# MCU.net
KiCad netlist of a schematic drawn in Altium Designer
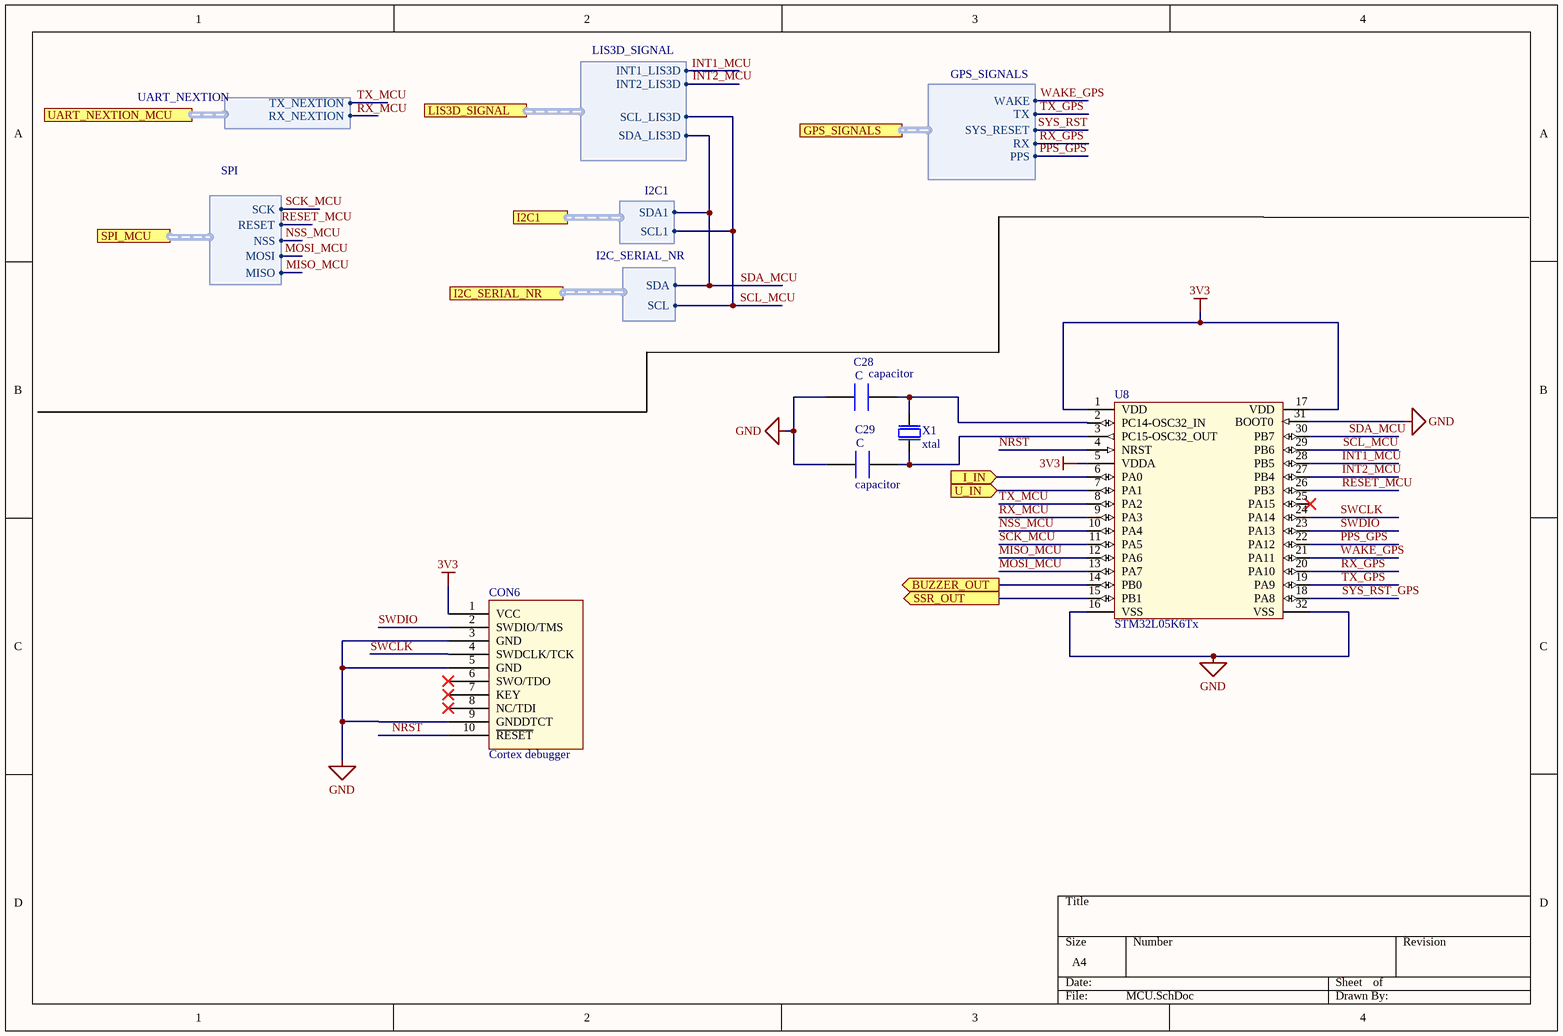
[diagram p0: MCU.SchDoc]

(export (version "E")
  (design (tool "Eeschema 10.0.6"))
  (components
    (comp (ref "C28")
      (value "capacitor")
      (footprint "CAPC1005X04L")
      (libsource (lib "pasives") (part "capacitor"))
    )
    (comp (ref "C29")
      (value "capacitor")
      (footprint "CAPC1005X04L")
      (libsource (lib "pasives") (part "capacitor"))
    )
    (comp (ref "CON6")
      (value "Cortex debugger")
      (footprint "Jtag header")
      (libsource (lib "conector's_and_TP") (part "Cortex debugger"))
    )
    (comp (ref "U8") (value "STM32L05K6Tx") (libsource (lib "halfgelijders") (part "STM32L05K6Tx")))
    (comp (ref "X1") (value "xtal") (footprint "BT-XTAL_2016") (libsource (lib "pasives") (part "xtal")))
  )
  (nets
    (net (code "9") (name "/BUZZER_OUT") (class "Default")
      (node (ref "U8") (pin "14") (pinfunction "PB0_14") (pintype "bidirectional"))
    )
    (net (code "11") (name "/INT1_MCU") (class "Default")
      (node (ref "U8") (pin "28") (pinfunction "PB5_28") (pintype "bidirectional"))
    )
    (net (code "12") (name "/INT2_MCU") (class "Default")
      (node (ref "U8") (pin "27") (pinfunction "PB4_27") (pintype "bidirectional"))
    )
    (net (code "13") (name "/I_IN") (class "Default")
      (node (ref "U8") (pin "6") (pinfunction "PA0_6") (pintype "bidirectional"))
    )
    (net (code "15") (name "/MISO_MCU") (class "Default")
      (node (ref "U8") (pin "12") (pinfunction "PA6_12") (pintype "bidirectional"))
    )
    (net (code "16") (name "/MOSI_MCU") (class "Default")
      (node (ref "U8") (pin "13") (pinfunction "PA7_13") (pintype "bidirectional"))
    )
    (net (code "17") (name "/NRST") (class "Default")
      (node (ref "CON6") (pin "10") (pinfunction "~{RESET}_10") (pintype "passive"))
      (node (ref "U8") (pin "4") (pinfunction "NRST_4") (pintype "input"))
    )
    (net (code "18") (name "/NSS_MCU") (class "Default")
      (node (ref "U8") (pin "10") (pinfunction "PA4_10") (pintype "bidirectional"))
    )
    (net (code "19") (name "/PPS_GPS") (class "Default")
      (node (ref "U8") (pin "22") (pinfunction "PA12_22") (pintype "bidirectional"))
    )
    (net (code "20") (name "/RESET_MCU") (class "Default")
      (node (ref "U8") (pin "26") (pinfunction "PB3_26") (pintype "bidirectional"))
    )
    (net (code "21") (name "/RX_GPS") (class "Default")
      (node (ref "U8") (pin "20") (pinfunction "PA10_20") (pintype "bidirectional"))
    )
    (net (code "22") (name "/RX_MCU") (class "Default")
      (node (ref "U8") (pin "9") (pinfunction "PA3_9") (pintype "bidirectional"))
    )
    (net (code "23") (name "/SCK_MCU") (class "Default")
      (node (ref "U8") (pin "11") (pinfunction "PA5_11") (pintype "bidirectional"))
    )
    (net (code "24") (name "/SCL_MCU") (class "Default")
      (node (ref "U8") (pin "29") (pinfunction "PB6_29") (pintype "bidirectional"))
    )
    (net (code "25") (name "/SDA_MCU") (class "Default")
      (node (ref "U8") (pin "30") (pinfunction "PB7_30") (pintype "bidirectional"))
    )
    (net (code "27") (name "/SSR_OUT") (class "Default")
      (node (ref "U8") (pin "15") (pinfunction "PB1_15") (pintype "bidirectional"))
    )
    (net (code "28") (name "/SWCLK") (class "Default")
      (node (ref "CON6") (pin "4") (pinfunction "SWDCLK/TCK_4") (pintype "passive"))
      (node (ref "U8") (pin "24") (pinfunction "PA14_24") (pintype "bidirectional"))
    )
    (net (code "29") (name "/SWDIO") (class "Default")
      (node (ref "CON6") (pin "2") (pinfunction "SWDIO/TMS_2") (pintype "passive"))
      (node (ref "U8") (pin "23") (pinfunction "PA13_23") (pintype "bidirectional"))
    )
    (net (code "31") (name "/SYS_RST_GPS") (class "Default")
      (node (ref "U8") (pin "18") (pinfunction "PA8_18") (pintype "bidirectional"))
    )
    (net (code "32") (name "/TX_GPS") (class "Default")
      (node (ref "U8") (pin "19") (pinfunction "PA9_19") (pintype "bidirectional"))
    )
    (net (code "33") (name "/TX_MCU") (class "Default")
      (node (ref "U8") (pin "8") (pinfunction "PA2_8") (pintype "bidirectional"))
    )
    (net (code "34") (name "/U_IN") (class "Default")
      (node (ref "U8") (pin "7") (pinfunction "PA1_7") (pintype "bidirectional"))
    )
    (net (code "35") (name "/WAKE_GPS") (class "Default")
      (node (ref "U8") (pin "21") (pinfunction "PA11_21") (pintype "bidirectional"))
    )
    (net (code "42") (name "3V3") (class "Default")
      (node (ref "CON6") (pin "1") (pinfunction "VCC_1") (pintype "passive"))
      (node (ref "U8") (pin "1") (pinfunction "VDD_1") (pintype "power_in"))
      (node (ref "U8") (pin "17") (pinfunction "VDD_17") (pintype "power_in"))
      (node (ref "U8") (pin "5") (pinfunction "VDDA_5") (pintype "power_in"))
    )
    (net (code "43") (name "GND") (class "Default")
      (node (ref "C28") (pin "2") (pinfunction "2_2") (pintype "passive"))
      (node (ref "C29") (pin "2") (pinfunction "2_2") (pintype "passive"))
      (node (ref "CON6") (pin "3") (pinfunction "GND_3") (pintype "passive"))
      (node (ref "CON6") (pin "5") (pinfunction "GND_5") (pintype "passive"))
      (node (ref "CON6") (pin "9") (pinfunction "GNDDTCT_9") (pintype "passive"))
      (node (ref "U8") (pin "16") (pinfunction "VSS_16") (pintype "power_in"))
      (node (ref "U8") (pin "31") (pinfunction "BOOT0_31") (pintype "input"))
      (node (ref "U8") (pin "32") (pinfunction "VSS_32") (pintype "power_in"))
    )
    (net (code "44") (name "Net-(U8-PC14-OSC32_IN)") (class "Default")
      (node (ref "C28") (pin "1") (pinfunction "1_1") (pintype "passive"))
      (node (ref "U8") (pin "2") (pinfunction "PC14-OSC32_IN_2") (pintype "bidirectional"))
      (node (ref "X1") (pin "3") (pinfunction "out_3") (pintype "passive"))
    )
    (net (code "45") (name "Net-(U8-PC15-OSC32_OUT)") (class "Default")
      (node (ref "C29") (pin "1") (pinfunction "1_1") (pintype "passive"))
      (node (ref "U8") (pin "3") (pinfunction "PC15-OSC32_OUT_3") (pintype "output"))
      (node (ref "X1") (pin "1") (pinfunction "inp_1") (pintype "passive"))
    )
    (net (code "46") (name "unconnected-(CON6-KEY-Pad7)") (class "Default")
      (node (ref "CON6") (pin "7") (pinfunction "KEY_7") (pintype "passive+no_connect"))
    )
    (net (code "47") (name "unconnected-(CON6-NC{slash}TDI-Pad8)") (class "Default")
      (node (ref "CON6") (pin "8") (pinfunction "NC/TDI_8") (pintype "passive+no_connect"))
    )
    (net (code "48") (name "unconnected-(CON6-SWO{slash}TDO-Pad6)") (class "Default")
      (node (ref "CON6") (pin "6") (pinfunction "SWO/TDO_6") (pintype "passive+no_connect"))
    )
    (net (code "49") (name "unconnected-(U8-PA15-Pad25)") (class "Default")
      (node (ref "U8") (pin "25") (pinfunction "PA15_25") (pintype "bidirectional+no_connect"))
    )
  )
)
